# Chassis.net
KiCad netlist of a schematic drawn in Altium Designer
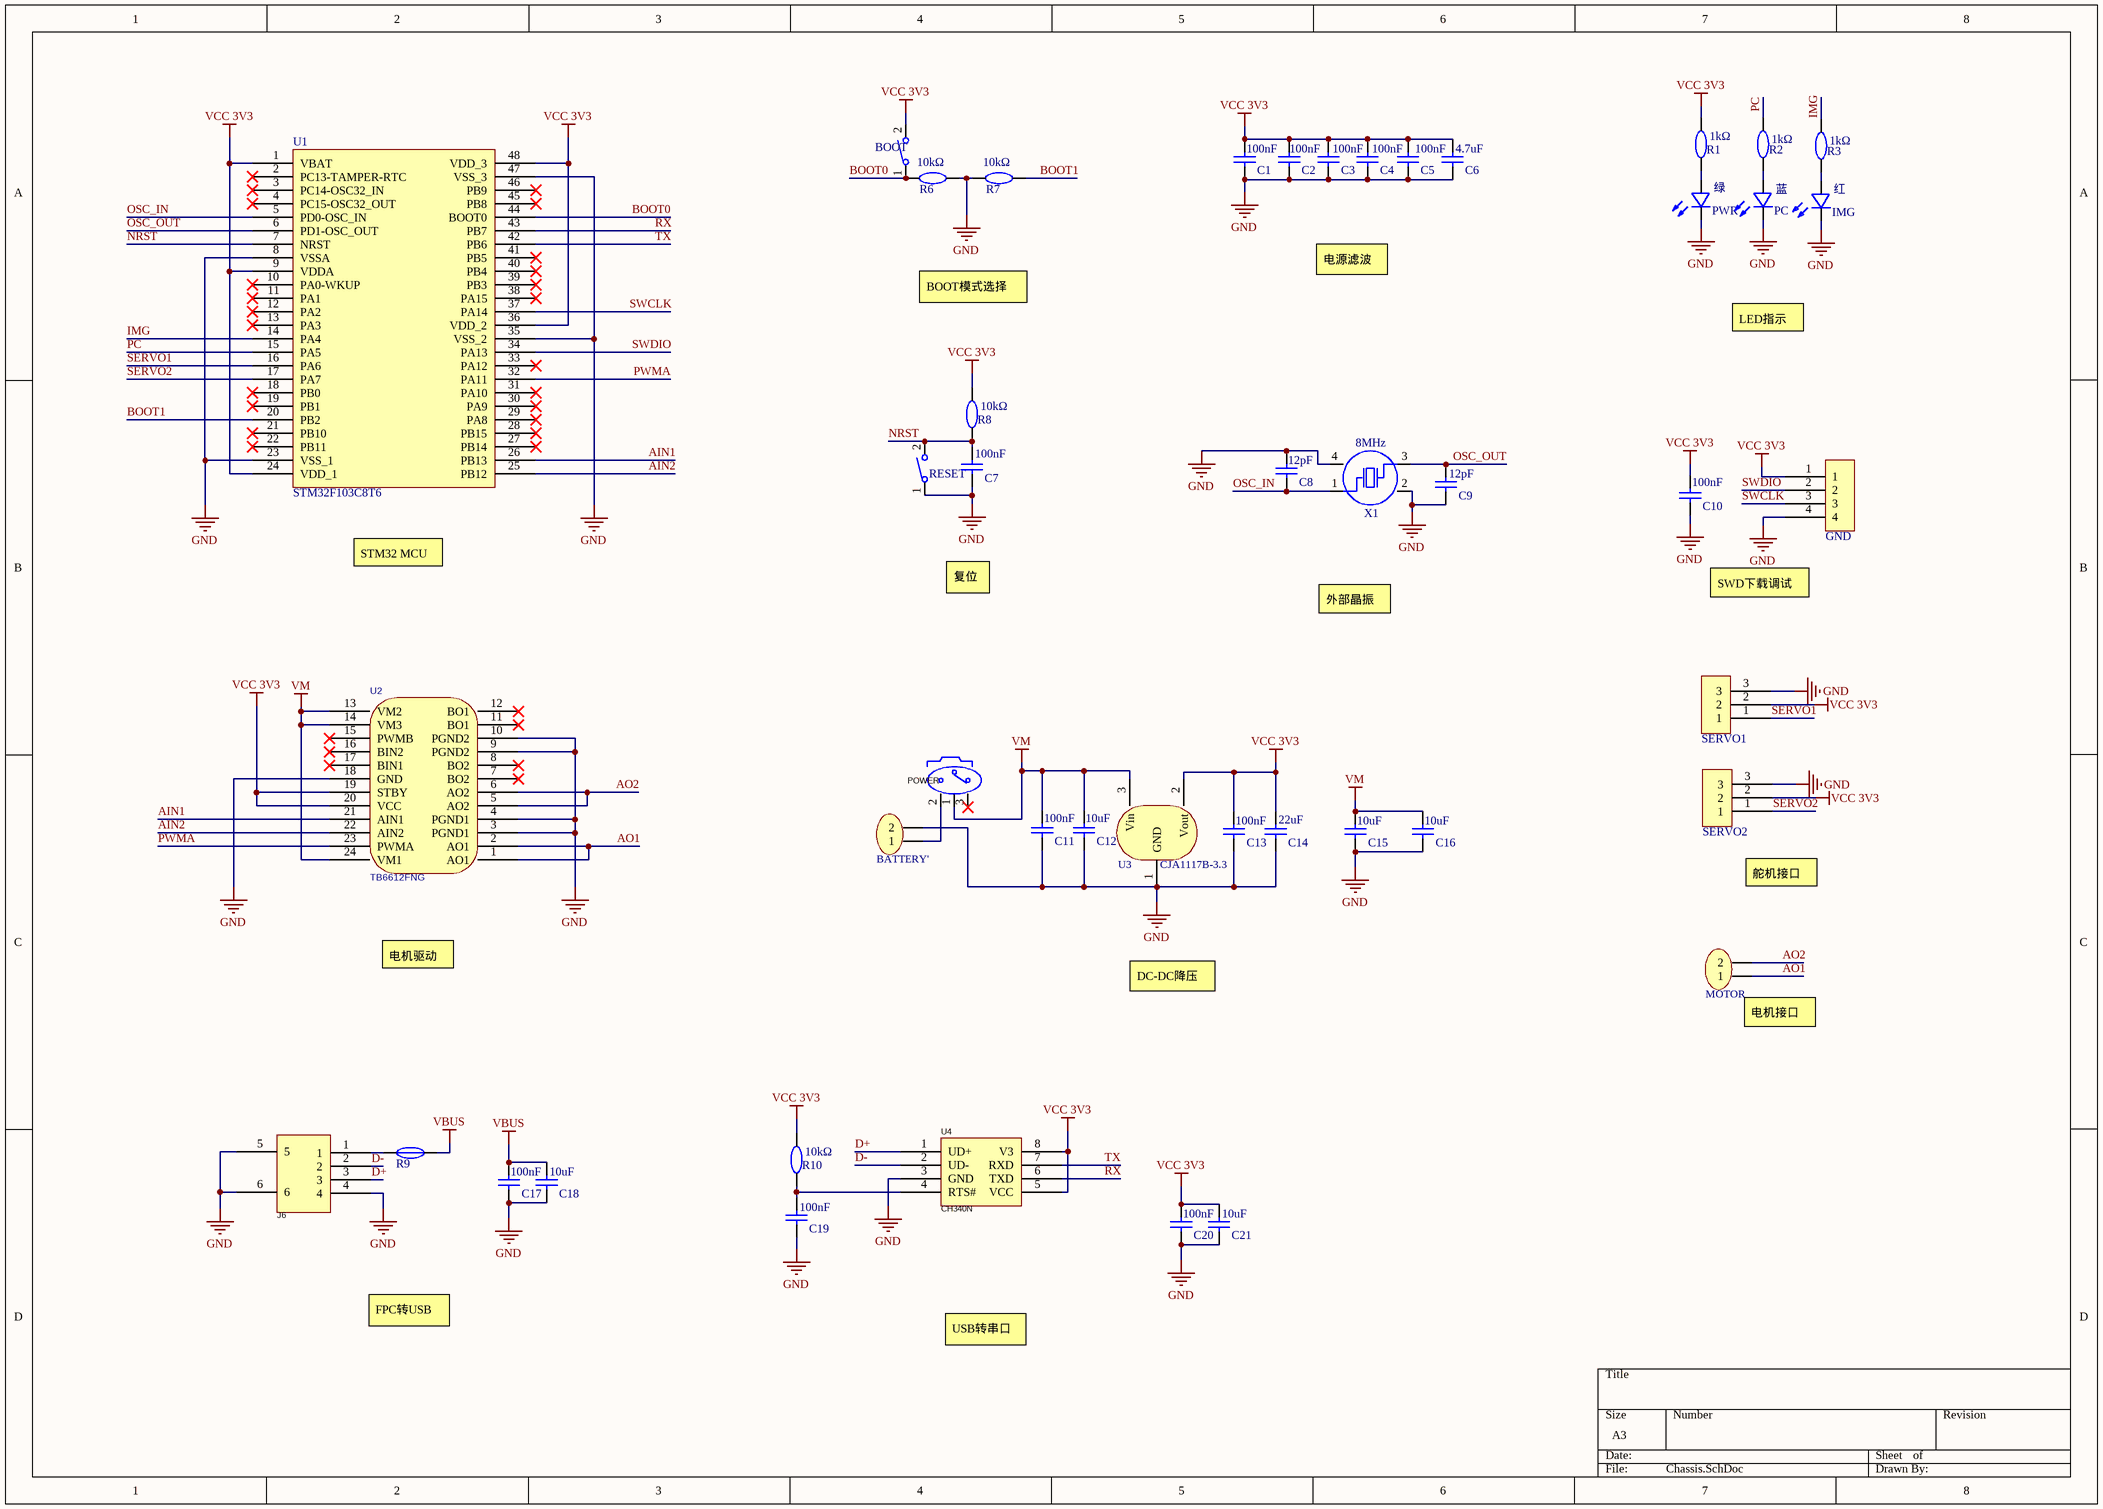
[diagram p0: Chassis.SchDoc]

(export (version "E")
  (design (tool "Eeschema 10.0.6"))
  (components
    (comp (ref "BATTERY'")
      (value "PH2.0-2pin")
      (footprint "CONN-TH_2P-P2.00_GP01-2001WR-2P")
      (description "PH2.0-2pin公头端子")
      (libsource (lib "Ruixiang_Lib") (part "PH2.0-2pin"))
    )
    (comp (ref "BOOT")
      (value "Switch")
      (footprint "KEY-SMD_2P-L6.0-W3.6-P7.4-LS8.0-L")
      (description "滑动开关")
      (fields
        (field (name "MANUFACTURER") "XKB Connectivity(中国星坤)")
        (field (name "MANUFACTURER PART") "TS-1101-B-W")
      )
      (libsource (lib "SchLib") (part "Switch"))
    )
    (comp (ref "C1")
      (value "CAP-0402")
      (footprint "C0402")
      (description "0402贴片电容")
      (fields
        (field (name "MANUFACTURER") "SAMSUNG(三星)")
        (field (name "MANUFACTURER PART") "CL21B104KBCNNNC")
      )
      (libsource (lib "Ruixiang_Lib") (part "CAP-0402"))
    )
    (comp (ref "C2")
      (value "CAP-0402")
      (footprint "C0402")
      (description "0402贴片电容")
      (fields
        (field (name "MANUFACTURER") "SAMSUNG(三星)")
        (field (name "MANUFACTURER PART") "CL21B104KBCNNNC")
      )
      (libsource (lib "Ruixiang_Lib") (part "CAP-0402"))
    )
    (comp (ref "C3")
      (value "CAP-0402")
      (footprint "C0402")
      (description "0402贴片电容")
      (fields
        (field (name "MANUFACTURER") "SAMSUNG(三星)")
        (field (name "MANUFACTURER PART") "CL21B104KBCNNNC")
      )
      (libsource (lib "Ruixiang_Lib") (part "CAP-0402"))
    )
    (comp (ref "C4")
      (value "CAP-0402")
      (footprint "C0402")
      (description "0402贴片电容")
      (fields
        (field (name "MANUFACTURER") "SAMSUNG(三星)")
        (field (name "MANUFACTURER PART") "CL21B104KBCNNNC")
      )
      (libsource (lib "Ruixiang_Lib") (part "CAP-0402"))
    )
    (comp (ref "C5")
      (value "CAP-0402")
      (footprint "C0402")
      (description "0402贴片电容")
      (fields
        (field (name "MANUFACTURER") "SAMSUNG(三星)")
        (field (name "MANUFACTURER PART") "CL21B104KBCNNNC")
      )
      (libsource (lib "Ruixiang_Lib") (part "CAP-0402"))
    )
    (comp (ref "C6")
      (value "CAP-0402")
      (footprint "C0402")
      (description "0402贴片电容")
      (fields
        (field (name "MANUFACTURER") "SAMSUNG(三星)")
        (field (name "MANUFACTURER PART") "CL21B104KBCNNNC")
      )
      (libsource (lib "Ruixiang_Lib") (part "CAP-0402"))
    )
    (comp (ref "C7")
      (value "CAP-0402")
      (footprint "C0402")
      (description "0402贴片电容")
      (fields
        (field (name "MANUFACTURER") "SAMSUNG(三星)")
        (field (name "MANUFACTURER PART") "CL21B104KBCNNNC")
      )
      (libsource (lib "Ruixiang_Lib") (part "CAP-0402"))
    )
    (comp (ref "C8")
      (value "CAP-0402")
      (footprint "C0402")
      (description "0402贴片电容")
      (fields
        (field (name "MANUFACTURER") "SAMSUNG(三星)")
        (field (name "MANUFACTURER PART") "CL21B104KBCNNNC")
      )
      (libsource (lib "Ruixiang_Lib") (part "CAP-0402"))
    )
    (comp (ref "C9")
      (value "CAP-0402")
      (footprint "C0402")
      (description "0402贴片电容")
      (fields
        (field (name "MANUFACTURER") "SAMSUNG(三星)")
        (field (name "MANUFACTURER PART") "CL21B104KBCNNNC")
      )
      (libsource (lib "Ruixiang_Lib") (part "CAP-0402"))
    )
    (comp (ref "C10")
      (value "CAP-0402")
      (footprint "C0402")
      (description "0402贴片电容")
      (fields
        (field (name "MANUFACTURER") "SAMSUNG(三星)")
        (field (name "MANUFACTURER PART") "CL21B104KBCNNNC")
      )
      (libsource (lib "Ruixiang_Lib") (part "CAP-0402"))
    )
    (comp (ref "C11")
      (value "CAP-0402")
      (footprint "C0402")
      (description "0402贴片电容")
      (fields
        (field (name "MANUFACTURER") "SAMSUNG(三星)")
        (field (name "MANUFACTURER PART") "CL21B104KBCNNNC")
      )
      (libsource (lib "Ruixiang_Lib") (part "CAP-0402"))
    )
    (comp (ref "C12")
      (value "CAP-0402")
      (footprint "C0402")
      (description "0402贴片电容")
      (fields
        (field (name "MANUFACTURER") "SAMSUNG(三星)")
        (field (name "MANUFACTURER PART") "CL21B104KBCNNNC")
      )
      (libsource (lib "Ruixiang_Lib") (part "CAP-0402"))
    )
    (comp (ref "C13")
      (value "CAP-0402")
      (footprint "C0402")
      (description "0402贴片电容")
      (fields
        (field (name "MANUFACTURER") "SAMSUNG(三星)")
        (field (name "MANUFACTURER PART") "CL21B104KBCNNNC")
      )
      (libsource (lib "Ruixiang_Lib") (part "CAP-0402"))
    )
    (comp (ref "C14")
      (value "CAP-0402")
      (footprint "C0402")
      (description "0402贴片电容")
      (fields
        (field (name "MANUFACTURER") "SAMSUNG(三星)")
        (field (name "MANUFACTURER PART") "CL21B104KBCNNNC")
      )
      (libsource (lib "Ruixiang_Lib") (part "CAP-0402"))
    )
    (comp (ref "C15")
      (value "CAP-0402")
      (footprint "C0402")
      (description "0402贴片电容")
      (fields
        (field (name "MANUFACTURER") "SAMSUNG(三星)")
        (field (name "MANUFACTURER PART") "CL21B104KBCNNNC")
      )
      (libsource (lib "Ruixiang_Lib") (part "CAP-0402"))
    )
    (comp (ref "C16")
      (value "CAP-0402")
      (footprint "C0402")
      (description "0402贴片电容")
      (fields
        (field (name "MANUFACTURER") "SAMSUNG(三星)")
        (field (name "MANUFACTURER PART") "CL21B104KBCNNNC")
      )
      (libsource (lib "Ruixiang_Lib") (part "CAP-0402"))
    )
    (comp (ref "C17")
      (value "CAP-0402")
      (footprint "C0402")
      (description "0402贴片电容")
      (fields
        (field (name "MANUFACTURER") "SAMSUNG(三星)")
        (field (name "MANUFACTURER PART") "CL21B104KBCNNNC")
      )
      (libsource (lib "Ruixiang_Lib") (part "CAP-0402"))
    )
    (comp (ref "C18")
      (value "CAP-0402")
      (footprint "C0402")
      (description "0402贴片电容")
      (fields
        (field (name "MANUFACTURER") "SAMSUNG(三星)")
        (field (name "MANUFACTURER PART") "CL21B104KBCNNNC")
      )
      (libsource (lib "Ruixiang_Lib") (part "CAP-0402"))
    )
    (comp (ref "C19")
      (value "CAP-0402")
      (footprint "C0402")
      (description "0402贴片电容")
      (fields
        (field (name "MANUFACTURER") "SAMSUNG(三星)")
        (field (name "MANUFACTURER PART") "CL21B104KBCNNNC")
      )
      (libsource (lib "Ruixiang_Lib") (part "CAP-0402"))
    )
    (comp (ref "C20")
      (value "CAP-0402")
      (footprint "C0402")
      (description "0402贴片电容")
      (fields
        (field (name "MANUFACTURER") "SAMSUNG(三星)")
        (field (name "MANUFACTURER PART") "CL21B104KBCNNNC")
      )
      (libsource (lib "Ruixiang_Lib") (part "CAP-0402"))
    )
    (comp (ref "C21")
      (value "CAP-0402")
      (footprint "C0402")
      (description "0402贴片电容")
      (fields
        (field (name "MANUFACTURER") "SAMSUNG(三星)")
        (field (name "MANUFACTURER PART") "CL21B104KBCNNNC")
      )
      (libsource (lib "Ruixiang_Lib") (part "CAP-0402"))
    )
    (comp (ref "GND")
      (value "HDR-1X4")
      (footprint "HDR-TH_4P-P2.54-H-M-W10.4")
      (description "1X4弯排针")
      (libsource (lib "SchLib") (part "HDR-1X4-弯排针"))
    )
    (comp (ref "IMG")
      (value "LED0805-RD")
      (footprint "LED0805-RD")
      (description "LED")
      (fields (field (name "MANUFACTURER") "MEIHUA(美华科技)") (field (name "MANUFACTURER PART") "MHT170UBCT"))
      (libsource (lib "Ruixiang_Lib") (part "LED0805-RD"))
    )
    (comp (ref "J6")
      (value "AFC01-S04FCC-00")
      (footprint "FFC-SMD_4P-P0.50_AFC01-S04FCC-00")
      (description "4pin FPC接口，间距0.5mm")
      (fields (field (name "MANUFACTURER") "JS(钜硕电子)"))
      (libsource (lib "Ruixiang_Lib") (part "FPC0.5-4pin"))
    )
    (comp (ref "MOTOR")
      (value "PH2.0-2pin")
      (footprint "CONN-TH_2P-P2.00_GP01-2001WR-2P")
      (description "PH2.0-2pin公头端子")
      (libsource (lib "Ruixiang_Lib") (part "PH2.0-2pin"))
    )
    (comp (ref "PC")
      (value "LED0805-RD")
      (footprint "LED0805-RD")
      (description "LED")
      (fields (field (name "MANUFACTURER") "MEIHUA(美华科技)") (field (name "MANUFACTURER PART") "MHT170UBCT"))
      (libsource (lib "Ruixiang_Lib") (part "LED0805-RD"))
    )
    (comp (ref "POWER")
      (value "BSI-10H")
      (footprint "SW-TH_BSI-10H")
      (description "三脚开关")
      (fields (field (name "MANUFACTURER") "SM Switch"))
      (libsource (lib "SchLib") (part "Switch-三脚开关"))
    )
    (comp (ref "PWR")
      (value "LED0805-RD")
      (footprint "LED0805-RD")
      (description "LED")
      (fields (field (name "MANUFACTURER") "MEIHUA(美华科技)") (field (name "MANUFACTURER PART") "MHT170UBCT"))
      (libsource (lib "Ruixiang_Lib") (part "LED0805-RD"))
    )
    (comp (ref "R1")
      (value "RES-0402")
      (footprint "R0402")
      (description "0402贴片电阻")
      (fields (field (name "MANUFACTURER") "FH(风华)") (field (name "MANUFACTURER PART") "RS-05K102JT"))
      (libsource (lib "Ruixiang_Lib") (part "RES-0402"))
    )
    (comp (ref "R2")
      (value "RES-0402")
      (footprint "R0402")
      (description "0402贴片电阻")
      (fields (field (name "MANUFACTURER") "FH(风华)") (field (name "MANUFACTURER PART") "RS-05K102JT"))
      (libsource (lib "Ruixiang_Lib") (part "RES-0402"))
    )
    (comp (ref "R3")
      (value "RES-0402")
      (footprint "R0402")
      (description "0402贴片电阻")
      (fields (field (name "MANUFACTURER") "FH(风华)") (field (name "MANUFACTURER PART") "RS-05K102JT"))
      (libsource (lib "Ruixiang_Lib") (part "RES-0402"))
    )
    (comp (ref "R6")
      (value "RES-0402")
      (footprint "R0402")
      (description "0402贴片电阻")
      (fields (field (name "MANUFACTURER") "FH(风华)") (field (name "MANUFACTURER PART") "RS-05K102JT"))
      (libsource (lib "Ruixiang_Lib") (part "RES-0402"))
    )
    (comp (ref "R7")
      (value "RES-0402")
      (footprint "R0402")
      (description "0402贴片电阻")
      (fields (field (name "MANUFACTURER") "FH(风华)") (field (name "MANUFACTURER PART") "RS-05K102JT"))
      (libsource (lib "Ruixiang_Lib") (part "RES-0402"))
    )
    (comp (ref "R8")
      (value "RES-0402")
      (footprint "R0402")
      (description "0402贴片电阻")
      (fields (field (name "MANUFACTURER") "FH(风华)") (field (name "MANUFACTURER PART") "RS-05K102JT"))
      (libsource (lib "Ruixiang_Lib") (part "RES-0402"))
    )
    (comp (ref "R9")
      (value "TLC F1206")
      (footprint "F1206")
      (description "保险丝")
      (fields (field (name "MANUFACTURER") "TLC(竞沃)") (field (name "MANUFACTURER PART") "TLC-NSMD100"))
      (libsource (lib "Ruixiang_Lib") (part "TLC F1206"))
    )
    (comp (ref "R10")
      (value "RES-0402")
      (footprint "R0402")
      (description "0402贴片电阻")
      (fields (field (name "MANUFACTURER") "FH(风华)") (field (name "MANUFACTURER PART") "RS-05K102JT"))
      (libsource (lib "Ruixiang_Lib") (part "RES-0402"))
    )
    (comp (ref "RESET")
      (value "Switch")
      (footprint "KEY-SMD_2P-L6.0-W3.6-P7.4-LS8.0-L")
      (description "滑动开关")
      (fields
        (field (name "MANUFACTURER") "XKB Connectivity(中国星坤)")
        (field (name "MANUFACTURER PART") "TS-1101-B-W")
      )
      (libsource (lib "SchLib") (part "Switch"))
    )
    (comp (ref "SERVO1")
      (value "MX1.25-3pin")
      (footprint "CONN-TH_3P-P1.25_BX-MX1.25-3PWZ")
      (description "MX1.25 3pin 公头端子")
      (libsource (lib "SchLib") (part "MX1.25-3pin"))
    )
    (comp (ref "SERVO2")
      (value "MX1.25-3pin")
      (footprint "CONN-TH_3P-P1.25_BX-MX1.25-3PWZ")
      (description "MX1.25 3pin 公头端子")
      (libsource (lib "SchLib") (part "MX1.25-3pin"))
    )
    (comp (ref "U1")
      (value "STM32F103C8T6")
      (footprint "LQFP-48_L7.0-W7.0-P0.50-LS9.0-BL")
      (description "STM32F103C8T6 MCU")
      (fields (field (name "MANUFACTURER") "ST(意法半导体)") (field (name "DEVICE") "STM32F103C8T6"))
      (libsource (lib "Ruixiang_Lib") (part "STM32F103C8T6"))
    )
    (comp (ref "U2")
      (value "TB6612FNG")
      (footprint "SSOP-24_L8.4-W5.8-P0.65-LS7.8-BL")
      (description "TB6612FNG电机驱动")
      (libsource (lib "SchLib") (part "TB6612FNG"))
    )
    (comp (ref "U3")
      (value "CJA1117B-3.3")
      (footprint "SOT-89")
      (description "3.3V线性稳压器")
      (libsource (lib "Ruixiang_Lib") (part "CJA1117B-3.3"))
    )
    (comp (ref "U4")
      (value "CH340N")
      (footprint "SOP-8_L4.9-W3.9-P1.27-LS6.0-BL")
      (description "USB转串口")
      (fields (field (name "MANUFACTURER") "WCH(南京沁恒)"))
      (libsource (lib "SchLib") (part "CH340N"))
    )
    (comp (ref "X1")
      (value "OSC CRYSTAL-SMD_4P-L3.2-W2.5-BL")
      (footprint "CRYSTAL-SMD_4P-L3.2-W2.5-BL")
      (description "四脚晶振")
      (fields (field (name "MANUFACTURER") "JGHC(晶光华)") (field (name "MANUFACTURER PART") "S3212000201080"))
      (libsource (lib "Ruixiang_Lib") (part "OSC CRYSTAL-SMD_4P-L3.2-W2.5-BL"))
    )
  )
  (nets
    (net (code "1") (name "/AIN1") (class "Default")
      (node (ref "U1") (pin "26") (pinfunction "PB13_26") (pintype "passive"))
      (node (ref "U2") (pin "21") (pinfunction "AIN1_21") (pintype "passive"))
    )
    (net (code "2") (name "/AIN2") (class "Default")
      (node (ref "U1") (pin "25") (pinfunction "PB12_25") (pintype "passive"))
      (node (ref "U2") (pin "22") (pinfunction "AIN2_22") (pintype "passive"))
    )
    (net (code "3") (name "/AO1") (class "Default")
      (node (ref "MOTOR") (pin "1") (pinfunction "1_1") (pintype "passive"))
      (node (ref "U2") (pin "1") (pinfunction "AO1_1") (pintype "passive"))
      (node (ref "U2") (pin "2") (pinfunction "AO1_2") (pintype "passive"))
    )
    (net (code "4") (name "/AO2") (class "Default")
      (node (ref "MOTOR") (pin "2") (pinfunction "2_2") (pintype "passive"))
      (node (ref "U2") (pin "5") (pinfunction "AO2_5") (pintype "passive"))
      (node (ref "U2") (pin "6") (pinfunction "AO2_6") (pintype "passive"))
    )
    (net (code "5") (name "/BOOT0") (class "Default")
      (node (ref "BOOT") (pin "1") (pinfunction "1_1") (pintype "passive"))
      (node (ref "R6") (pin "1") (pinfunction "1_1") (pintype "passive"))
      (node (ref "U1") (pin "44") (pinfunction "BOOT0_44") (pintype "passive"))
    )
    (net (code "6") (name "/BOOT1") (class "Default")
      (node (ref "R7") (pin "2") (pinfunction "2_2") (pintype "passive"))
      (node (ref "U1") (pin "20") (pinfunction "PB2_20") (pintype "passive"))
    )
    (net (code "7") (name "/D+") (class "Default")
      (node (ref "J6") (pin "3") (pinfunction "3_3") (pintype "passive"))
      (node (ref "U4") (pin "1") (pinfunction "UD+_1") (pintype "passive"))
    )
    (net (code "8") (name "/D-") (class "Default")
      (node (ref "J6") (pin "2") (pinfunction "2_2") (pintype "passive"))
      (node (ref "U4") (pin "2") (pinfunction "UD-_2") (pintype "passive"))
    )
    (net (code "9") (name "/IMG") (class "Default")
      (node (ref "R3") (pin "2") (pinfunction "2_2") (pintype "passive"))
      (node (ref "U1") (pin "14") (pinfunction "PA4_14") (pintype "passive"))
    )
    (net (code "10") (name "/NRST") (class "Default")
      (node (ref "C7") (pin "2") (pinfunction "2_2") (pintype "passive"))
      (node (ref "R8") (pin "1") (pinfunction "1_1") (pintype "passive"))
      (node (ref "RESET") (pin "2") (pinfunction "2_2") (pintype "passive"))
      (node (ref "U1") (pin "7") (pinfunction "NRST_7") (pintype "passive"))
    )
    (net (code "11") (name "/OSC_IN") (class "Default")
      (node (ref "C8") (pin "1") (pinfunction "1_1") (pintype "passive"))
      (node (ref "U1") (pin "5") (pinfunction "PD0-OSC_IN_5") (pintype "passive"))
      (node (ref "X1") (pin "1") (pinfunction "OSC1_1") (pintype "passive"))
    )
    (net (code "12") (name "/OSC_OUT") (class "Default")
      (node (ref "C9") (pin "2") (pinfunction "2_2") (pintype "passive"))
      (node (ref "U1") (pin "6") (pinfunction "PD1-OSC_OUT_6") (pintype "passive"))
      (node (ref "X1") (pin "3") (pinfunction "OSC2_3") (pintype "passive"))
    )
    (net (code "13") (name "/PC") (class "Default")
      (node (ref "R2") (pin "2") (pinfunction "2_2") (pintype "passive"))
      (node (ref "U1") (pin "15") (pinfunction "PA5_15") (pintype "passive"))
    )
    (net (code "14") (name "/PWMA") (class "Default")
      (node (ref "U1") (pin "32") (pinfunction "PA11_32") (pintype "passive"))
      (node (ref "U2") (pin "23") (pinfunction "PWMA_23") (pintype "passive"))
    )
    (net (code "15") (name "/RX") (class "Default")
      (node (ref "U1") (pin "43") (pinfunction "PB7_43") (pintype "passive"))
      (node (ref "U4") (pin "6") (pinfunction "TXD_6") (pintype "passive"))
    )
    (net (code "16") (name "/SERVO1") (class "Default")
      (node (ref "SERVO1") (pin "1") (pinfunction "1_1") (pintype "passive"))
      (node (ref "U1") (pin "16") (pinfunction "PA6_16") (pintype "passive"))
    )
    (net (code "17") (name "/SERVO2") (class "Default")
      (node (ref "SERVO2") (pin "1") (pinfunction "1_1") (pintype "passive"))
      (node (ref "U1") (pin "17") (pinfunction "PA7_17") (pintype "passive"))
    )
    (net (code "18") (name "/SWCLK") (class "Default")
      (node (ref "GND") (pin "3") (pinfunction "3_3") (pintype "passive"))
      (node (ref "U1") (pin "37") (pinfunction "PA14_37") (pintype "passive"))
    )
    (net (code "19") (name "/SWDIO") (class "Default")
      (node (ref "GND") (pin "2") (pinfunction "2_2") (pintype "passive"))
      (node (ref "U1") (pin "34") (pinfunction "PA13_34") (pintype "passive"))
    )
    (net (code "20") (name "/TX") (class "Default")
      (node (ref "U1") (pin "42") (pinfunction "PB6_42") (pintype "passive"))
      (node (ref "U4") (pin "7") (pinfunction "RXD_7") (pintype "passive"))
    )
    (net (code "21") (name "GND") (class "Default")
      (node (ref "BATTERY'") (pin "2") (pinfunction "2_2") (pintype "passive"))
      (node (ref "C1") (pin "1") (pinfunction "1_1") (pintype "passive"))
      (node (ref "C10") (pin "1") (pinfunction "1_1") (pintype "passive"))
      (node (ref "C11") (pin "1") (pinfunction "1_1") (pintype "passive"))
      (node (ref "C12") (pin "1") (pinfunction "1_1") (pintype "passive"))
      (node (ref "C13") (pin "1") (pinfunction "1_1") (pintype "passive"))
      (node (ref "C14") (pin "1") (pinfunction "1_1") (pintype "passive"))
      (node (ref "C15") (pin "1") (pinfunction "1_1") (pintype "passive"))
      (node (ref "C16") (pin "1") (pinfunction "1_1") (pintype "passive"))
      (node (ref "C17") (pin "1") (pinfunction "1_1") (pintype "passive"))
      (node (ref "C18") (pin "1") (pinfunction "1_1") (pintype "passive"))
      (node (ref "C19") (pin "1") (pinfunction "1_1") (pintype "passive"))
      (node (ref "C2") (pin "1") (pinfunction "1_1") (pintype "passive"))
      (node (ref "C20") (pin "1") (pinfunction "1_1") (pintype "passive"))
      (node (ref "C21") (pin "1") (pinfunction "1_1") (pintype "passive"))
      (node (ref "C3") (pin "1") (pinfunction "1_1") (pintype "passive"))
      (node (ref "C4") (pin "1") (pinfunction "1_1") (pintype "passive"))
      (node (ref "C5") (pin "1") (pinfunction "1_1") (pintype "passive"))
      (node (ref "C6") (pin "1") (pinfunction "1_1") (pintype "passive"))
      (node (ref "C7") (pin "1") (pinfunction "1_1") (pintype "passive"))
      (node (ref "C8") (pin "2") (pinfunction "2_2") (pintype "passive"))
      (node (ref "C9") (pin "1") (pinfunction "1_1") (pintype "passive"))
      (node (ref "GND") (pin "4") (pinfunction "4_4") (pintype "passive"))
      (node (ref "IMG") (pin "1") (pinfunction "-_1") (pintype "passive"))
      (node (ref "J6") (pin "4") (pinfunction "4_4") (pintype "passive"))
      (node (ref "J6") (pin "5") (pinfunction "5_5") (pintype "passive"))
      (node (ref "J6") (pin "6") (pinfunction "6_6") (pintype "passive"))
      (node (ref "PC") (pin "1") (pinfunction "-_1") (pintype "passive"))
      (node (ref "PWR") (pin "1") (pinfunction "-_1") (pintype "passive"))
      (node (ref "R6") (pin "2") (pinfunction "2_2") (pintype "passive"))
      (node (ref "R7") (pin "1") (pinfunction "1_1") (pintype "passive"))
      (node (ref "RESET") (pin "1") (pinfunction "1_1") (pintype "passive"))
      (node (ref "SERVO1") (pin "3") (pinfunction "3_3") (pintype "passive"))
      (node (ref "SERVO2") (pin "3") (pinfunction "3_3") (pintype "passive"))
      (node (ref "U1") (pin "23") (pinfunction "VSS_1_23") (pintype "passive"))
      (node (ref "U1") (pin "35") (pinfunction "VSS_2_35") (pintype "passive"))
      (node (ref "U1") (pin "47") (pinfunction "VSS_3_47") (pintype "passive"))
      (node (ref "U1") (pin "8") (pinfunction "VSSA_8") (pintype "passive"))
      (node (ref "U2") (pin "10") (pinfunction "PGND2_10") (pintype "passive"))
      (node (ref "U2") (pin "18") (pinfunction "GND_18") (pintype "passive"))
      (node (ref "U2") (pin "3") (pinfunction "PGND1_3") (pintype "passive"))
      (node (ref "U2") (pin "4") (pinfunction "PGND1_4") (pintype "passive"))
      (node (ref "U2") (pin "9") (pinfunction "PGND2_9") (pintype "passive"))
      (node (ref "U3") (pin "1") (pinfunction "GND_1") (pintype "passive"))
      (node (ref "U4") (pin "3") (pinfunction "GND_3") (pintype "passive"))
      (node (ref "X1") (pin "2") (pinfunction "GND_2") (pintype "passive"))
      (node (ref "X1") (pin "4") (pinfunction "GND_4") (pintype "passive"))
    )
    (net (code "22") (name "Net-(BATTERY'-Pad1)") (class "Default")
      (node (ref "BATTERY'") (pin "1") (pinfunction "1_1") (pintype "passive"))
      (node (ref "POWER") (pin "2") (pinfunction "2_2") (pintype "passive"))
    )
    (net (code "23") (name "Net-(IMG-+)") (class "Default")
      (node (ref "IMG") (pin "2") (pinfunction "+_2") (pintype "passive"))
      (node (ref "R3") (pin "1") (pinfunction "1_1") (pintype "passive"))
    )
    (net (code "24") (name "Net-(J6-Pad1)") (class "Default")
      (node (ref "J6") (pin "1") (pinfunction "1_1") (pintype "passive"))
      (node (ref "R9") (pin "1") (pinfunction "1_1") (pintype "passive"))
    )
    (net (code "25") (name "Net-(PC-+)") (class "Default")
      (node (ref "PC") (pin "2") (pinfunction "+_2") (pintype "passive"))
      (node (ref "R2") (pin "1") (pinfunction "1_1") (pintype "passive"))
    )
    (net (code "26") (name "Net-(PWR-+)") (class "Default")
      (node (ref "PWR") (pin "2") (pinfunction "+_2") (pintype "passive"))
      (node (ref "R1") (pin "1") (pinfunction "1_1") (pintype "passive"))
    )
    (net (code "27") (name "Net-(U4-RTS#)") (class "Default")
      (node (ref "C19") (pin "2") (pinfunction "2_2") (pintype "passive"))
      (node (ref "R10") (pin "1") (pinfunction "1_1") (pintype "passive"))
      (node (ref "U4") (pin "4") (pinfunction "RTS#_4") (pintype "passive"))
    )
    (net (code "28") (name "VBUS") (class "Default")
      (node (ref "C17") (pin "2") (pinfunction "2_2") (pintype "passive"))
      (node (ref "C18") (pin "2") (pinfunction "2_2") (pintype "passive"))
      (node (ref "R9") (pin "2") (pinfunction "2_2") (pintype "passive"))
    )
    (net (code "29") (name "VCC 3V3") (class "Default")
      (node (ref "BOOT") (pin "2") (pinfunction "2_2") (pintype "passive"))
      (node (ref "C1") (pin "2") (pinfunction "2_2") (pintype "passive"))
      (node (ref "C10") (pin "2") (pinfunction "2_2") (pintype "passive"))
      (node (ref "C13") (pin "2") (pinfunction "2_2") (pintype "passive"))
      (node (ref "C14") (pin "2") (pinfunction "2_2") (pintype "passive"))
      (node (ref "C2") (pin "2") (pinfunction "2_2") (pintype "passive"))
      (node (ref "C20") (pin "2") (pinfunction "2_2") (pintype "passive"))
      (node (ref "C21") (pin "2") (pinfunction "2_2") (pintype "passive"))
      (node (ref "C3") (pin "2") (pinfunction "2_2") (pintype "passive"))
      (node (ref "C4") (pin "2") (pinfunction "2_2") (pintype "passive"))
      (node (ref "C5") (pin "2") (pinfunction "2_2") (pintype "passive"))
      (node (ref "C6") (pin "2") (pinfunction "2_2") (pintype "passive"))
      (node (ref "GND") (pin "1") (pinfunction "1_1") (pintype "passive"))
      (node (ref "R1") (pin "2") (pinfunction "2_2") (pintype "passive"))
      (node (ref "R10") (pin "2") (pinfunction "2_2") (pintype "passive"))
      (node (ref "R8") (pin "2") (pinfunction "2_2") (pintype "passive"))
      (node (ref "SERVO1") (pin "2") (pinfunction "2_2") (pintype "passive"))
      (node (ref "SERVO2") (pin "2") (pinfunction "2_2") (pintype "passive"))
      (node (ref "U1") (pin "1") (pinfunction "VBAT_1") (pintype "passive"))
      (node (ref "U1") (pin "24") (pinfunction "VDD_1_24") (pintype "passive"))
      (node (ref "U1") (pin "36") (pinfunction "VDD_2_36") (pintype "passive"))
      (node (ref "U1") (pin "48") (pinfunction "VDD_3_48") (pintype "passive"))
      (node (ref "U1") (pin "9") (pinfunction "VDDA_9") (pintype "passive"))
      (node (ref "U2") (pin "19") (pinfunction "STBY_19") (pintype "passive"))
      (node (ref "U2") (pin "20") (pinfunction "VCC_20") (pintype "passive"))
      (node (ref "U3") (pin "2") (pinfunction "Vout_2") (pintype "passive"))
      (node (ref "U4") (pin "5") (pinfunction "VCC_5") (pintype "passive"))
      (node (ref "U4") (pin "8") (pinfunction "V3_8") (pintype "passive"))
    )
    (net (code "30") (name "VM") (class "Default")
      (node (ref "C11") (pin "2") (pinfunction "2_2") (pintype "passive"))
      (node (ref "C12") (pin "2") (pinfunction "2_2") (pintype "passive"))
      (node (ref "C15") (pin "2") (pinfunction "2_2") (pintype "passive"))
      (node (ref "C16") (pin "2") (pinfunction "2_2") (pintype "passive"))
      (node (ref "POWER") (pin "1") (pinfunction "1_1") (pintype "passive"))
      (node (ref "U2") (pin "13") (pinfunction "VM2_13") (pintype "passive"))
      (node (ref "U2") (pin "14") (pinfunction "VM3_14") (pintype "passive"))
      (node (ref "U2") (pin "24") (pinfunction "VM1_24") (pintype "passive"))
      (node (ref "U3") (pin "3") (pinfunction "Vin_3") (pintype "passive"))
    )
    (net (code "31") (name "unconnected-(POWER-Pad3)") (class "Default")
      (node (ref "POWER") (pin "3") (pinfunction "3_3") (pintype "passive+no_connect"))
    )
    (net (code "32") (name "unconnected-(U1-PA0-WKUP-Pad10)") (class "Default")
      (node (ref "U1") (pin "10") (pinfunction "PA0-WKUP_10") (pintype "passive+no_connect"))
    )
    (net (code "33") (name "unconnected-(U1-PA1-Pad11)") (class "Default")
      (node (ref "U1") (pin "11") (pinfunction "PA1_11") (pintype "passive+no_connect"))
    )
    (net (code "34") (name "unconnected-(U1-PA2-Pad12)") (class "Default")
      (node (ref "U1") (pin "12") (pinfunction "PA2_12") (pintype "passive+no_connect"))
    )
    (net (code "35") (name "unconnected-(U1-PA3-Pad13)") (class "Default")
      (node (ref "U1") (pin "13") (pinfunction "PA3_13") (pintype "passive+no_connect"))
    )
    (net (code "36") (name "unconnected-(U1-PA8-Pad29)") (class "Default")
      (node (ref "U1") (pin "29") (pinfunction "PA8_29") (pintype "passive+no_connect"))
    )
    (net (code "37") (name "unconnected-(U1-PA9-Pad30)") (class "Default")
      (node (ref "U1") (pin "30") (pinfunction "PA9_30") (pintype "passive+no_connect"))
    )
    (net (code "38") (name "unconnected-(U1-PA10-Pad31)") (class "Default")
      (node (ref "U1") (pin "31") (pinfunction "PA10_31") (pintype "passive+no_connect"))
    )
    (net (code "39") (name "unconnected-(U1-PA12-Pad33)") (class "Default")
      (node (ref "U1") (pin "33") (pinfunction "PA12_33") (pintype "passive+no_connect"))
    )
    (net (code "40") (name "unconnected-(U1-PA15-Pad38)") (class "Default")
      (node (ref "U1") (pin "38") (pinfunction "PA15_38") (pintype "passive+no_connect"))
    )
    (net (code "41") (name "unconnected-(U1-PB0-Pad18)") (class "Default")
      (node (ref "U1") (pin "18") (pinfunction "PB0_18") (pintype "passive+no_connect"))
    )
    (net (code "42") (name "unconnected-(U1-PB1-Pad19)") (class "Default")
      (node (ref "U1") (pin "19") (pinfunction "PB1_19") (pintype "passive+no_connect"))
    )
    (net (code "43") (name "unconnected-(U1-PB3-Pad39)") (class "Default")
      (node (ref "U1") (pin "39") (pinfunction "PB3_39") (pintype "passive+no_connect"))
    )
    (net (code "44") (name "unconnected-(U1-PB4-Pad40)") (class "Default")
      (node (ref "U1") (pin "40") (pinfunction "PB4_40") (pintype "passive+no_connect"))
    )
    (net (code "45") (name "unconnected-(U1-PB5-Pad41)") (class "Default")
      (node (ref "U1") (pin "41") (pinfunction "PB5_41") (pintype "passive+no_connect"))
    )
    (net (code "46") (name "unconnected-(U1-PB8-Pad45)") (class "Default")
      (node (ref "U1") (pin "45") (pinfunction "PB8_45") (pintype "passive+no_connect"))
    )
    (net (code "47") (name "unconnected-(U1-PB9-Pad46)") (class "Default")
      (node (ref "U1") (pin "46") (pinfunction "PB9_46") (pintype "passive+no_connect"))
    )
    (net (code "48") (name "unconnected-(U1-PB10-Pad21)") (class "Default")
      (node (ref "U1") (pin "21") (pinfunction "PB10_21") (pintype "passive+no_connect"))
    )
    (net (code "49") (name "unconnected-(U1-PB11-Pad22)") (class "Default")
      (node (ref "U1") (pin "22") (pinfunction "PB11_22") (pintype "passive+no_connect"))
    )
    (net (code "50") (name "unconnected-(U1-PB14-Pad27)") (class "Default")
      (node (ref "U1") (pin "27") (pinfunction "PB14_27") (pintype "passive+no_connect"))
    )
    (net (code "51") (name "unconnected-(U1-PB15-Pad28)") (class "Default")
      (node (ref "U1") (pin "28") (pinfunction "PB15_28") (pintype "passive+no_connect"))
    )
    (net (code "52") (name "unconnected-(U1-PC13-TAMPER-RTC-Pad2)") (class "Default")
      (node (ref "U1") (pin "2") (pinfunction "PC13-TAMPER-RTC_2") (pintype "passive+no_connect"))
    )
    (net (code "53") (name "unconnected-(U1-PC14-OSC32_IN-Pad3)") (class "Default")
      (node (ref "U1") (pin "3") (pinfunction "PC14-OSC32_IN_3") (pintype "passive+no_connect"))
    )
    (net (code "54") (name "unconnected-(U1-PC15-OSC32_OUT-Pad4)") (class "Default")
      (node (ref "U1") (pin "4") (pinfunction "PC15-OSC32_OUT_4") (pintype "passive+no_connect"))
    )
    (net (code "55") (name "unconnected-(U2-BIN1-Pad17)") (class "Default")
      (node (ref "U2") (pin "17") (pinfunction "BIN1_17") (pintype "passive+no_connect"))
    )
    (net (code "56") (name "unconnected-(U2-BIN2-Pad16)") (class "Default")
      (node (ref "U2") (pin "16") (pinfunction "BIN2_16") (pintype "passive+no_connect"))
    )
    (net (code "57") (name "unconnected-(U2-BO1-Pad11)") (class "Default")
      (node (ref "U2") (pin "11") (pinfunction "BO1_11") (pintype "passive+no_connect"))
    )
    (net (code "58") (name "unconnected-(U2-BO1-Pad12)") (class "Default")
      (node (ref "U2") (pin "12") (pinfunction "BO1_12") (pintype "passive+no_connect"))
    )
    (net (code "59") (name "unconnected-(U2-BO2-Pad7)") (class "Default")
      (node (ref "U2") (pin "7") (pinfunction "BO2_7") (pintype "passive+no_connect"))
    )
    (net (code "60") (name "unconnected-(U2-BO2-Pad8)") (class "Default")
      (node (ref "U2") (pin "8") (pinfunction "BO2_8") (pintype "passive+no_connect"))
    )
    (net (code "61") (name "unconnected-(U2-PWMB-Pad15)") (class "Default")
      (node (ref "U2") (pin "15") (pinfunction "PWMB_15") (pintype "passive+no_connect"))
    )
  )
)
